# Sheet9.net
KiCad netlist of a schematic drawn in Altium Designer
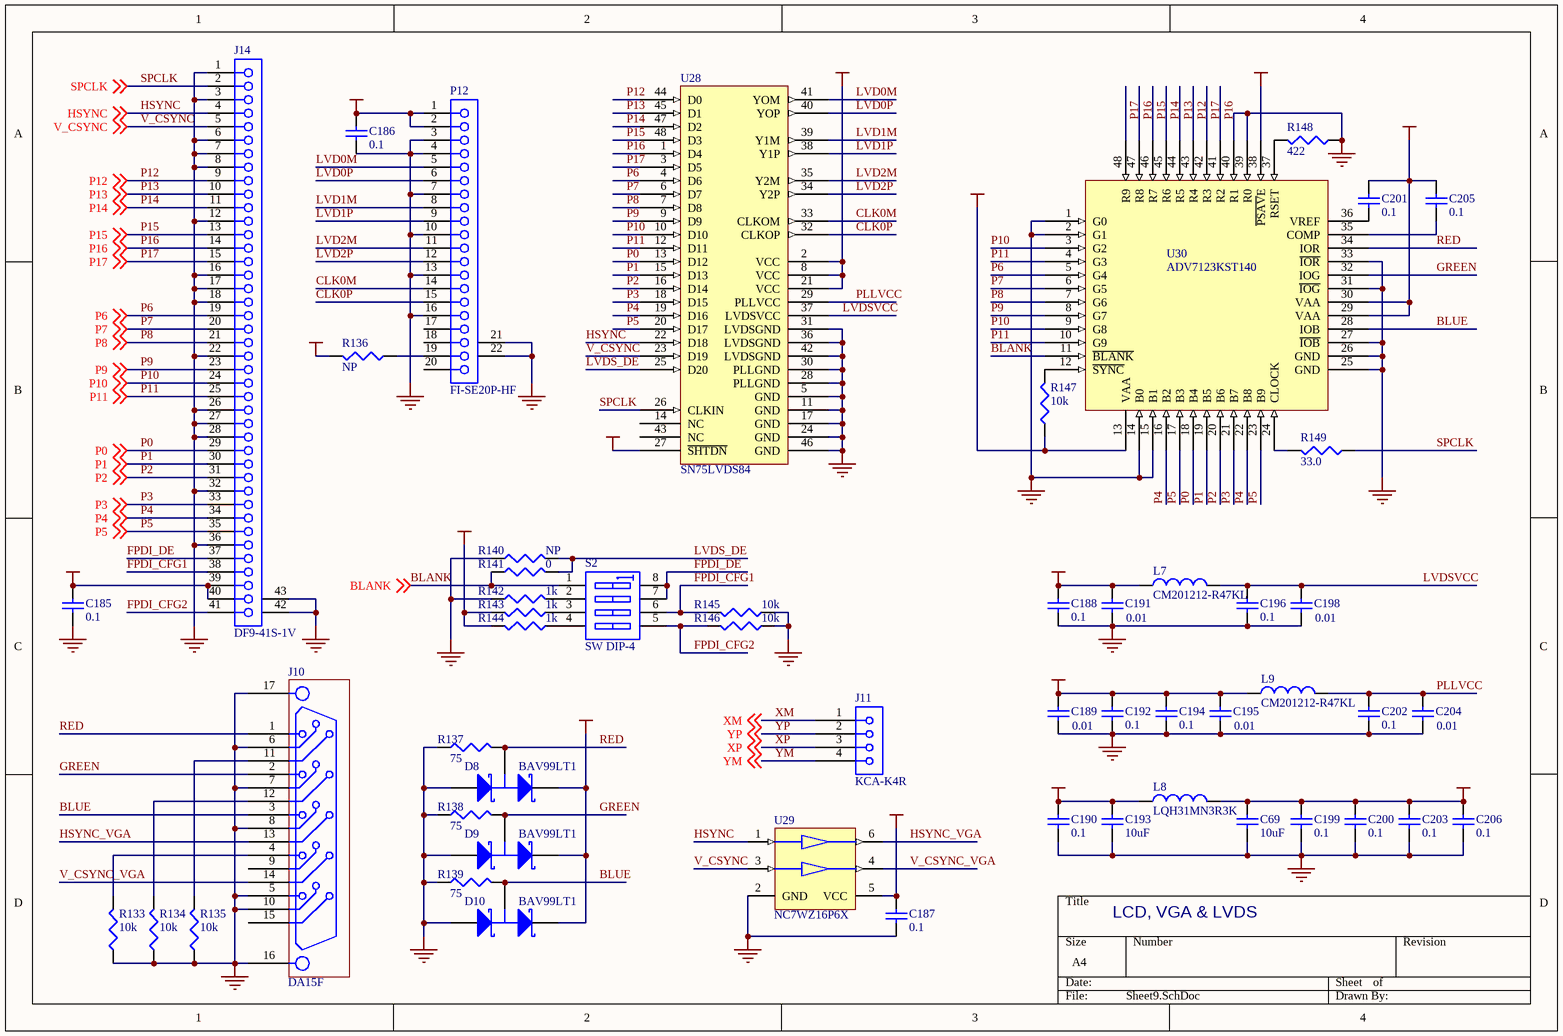
[diagram p0: Sheet9.SchDoc]

(export (version "E")
  (design (tool "Eeschema 10.0.6"))
  (components
    (comp (ref "C69")
      (value "10uF")
      (footprint "1206")
      (description "Ceramic Chip Capacitor - Standard")
      (fields (field (name "PUBLISHER") "Altium Limited"))
      (libsource (lib "KEMET Chip Capacitor") (part "C1206"))
    )
    (comp (ref "C185")
      (value "0.1")
      (footprint "0603")
      (description "Ceramic Chip Capacitor - Standard")
      (fields (field (name "PUBLISHER") "Altium Limited"))
      (libsource (lib "KEMET Chip Capacitor") (part "C0603"))
    )
    (comp (ref "C186")
      (value "0.1")
      (footprint "0603")
      (description "Ceramic Chip Capacitor - Standard")
      (fields (field (name "PUBLISHER") "Altium Limited"))
      (libsource (lib "KEMET Chip Capacitor") (part "C0603"))
    )
    (comp (ref "C187")
      (value "0.1")
      (footprint "0603")
      (description "Ceramic Chip Capacitor - Standard")
      (fields (field (name "PUBLISHER") "Altium Limited"))
      (libsource (lib "KEMET Chip Capacitor") (part "C0603"))
    )
    (comp (ref "C188")
      (value "0.1")
      (footprint "0603")
      (description "Ceramic Chip Capacitor - Standard")
      (fields (field (name "PUBLISHER") "Altium Limited"))
      (libsource (lib "KEMET Chip Capacitor") (part "C0603"))
    )
    (comp (ref "C189")
      (value "0.01")
      (footprint "0603")
      (description "Ceramic Chip Capacitor - Standard")
      (fields (field (name "PUBLISHER") "Altium Limited"))
      (libsource (lib "KEMET Chip Capacitor") (part "C0603"))
    )
    (comp (ref "C190")
      (value "0.1")
      (footprint "0603")
      (description "Ceramic Chip Capacitor - Standard")
      (fields (field (name "PUBLISHER") "Altium Limited"))
      (libsource (lib "KEMET Chip Capacitor") (part "C0603"))
    )
    (comp (ref "C191")
      (value "0.01")
      (footprint "0603")
      (description "Ceramic Chip Capacitor - Standard")
      (fields (field (name "PUBLISHER") "Altium Limited"))
      (libsource (lib "KEMET Chip Capacitor") (part "C0603"))
    )
    (comp (ref "C192")
      (value "0.1")
      (footprint "0603")
      (description "Ceramic Chip Capacitor - Standard")
      (fields (field (name "PUBLISHER") "Altium Limited"))
      (libsource (lib "KEMET Chip Capacitor") (part "C0603"))
    )
    (comp (ref "C193")
      (value "10uF")
      (footprint "1206")
      (description "Ceramic Chip Capacitor - Standard")
      (fields (field (name "PUBLISHER") "Altium Limited"))
      (libsource (lib "KEMET Chip Capacitor") (part "C1206"))
    )
    (comp (ref "C194")
      (value "0.1")
      (footprint "0603")
      (description "Ceramic Chip Capacitor - Standard")
      (fields (field (name "PUBLISHER") "Altium Limited"))
      (libsource (lib "KEMET Chip Capacitor") (part "C0603"))
    )
    (comp (ref "C195")
      (value "0.01")
      (footprint "0603")
      (description "Ceramic Chip Capacitor - Standard")
      (fields (field (name "PUBLISHER") "Altium Limited"))
      (libsource (lib "KEMET Chip Capacitor") (part "C0603"))
    )
    (comp (ref "C196")
      (value "0.1")
      (footprint "0603")
      (description "Ceramic Chip Capacitor - Standard")
      (fields (field (name "PUBLISHER") "Altium Limited"))
      (libsource (lib "KEMET Chip Capacitor") (part "C0603"))
    )
    (comp (ref "C198")
      (value "0.01")
      (footprint "0603")
      (description "Ceramic Chip Capacitor - Standard")
      (fields (field (name "PUBLISHER") "Altium Limited"))
      (libsource (lib "KEMET Chip Capacitor") (part "C0603"))
    )
    (comp (ref "C199")
      (value "0.1")
      (footprint "0603")
      (description "Ceramic Chip Capacitor - Standard")
      (fields (field (name "PUBLISHER") "Altium Limited"))
      (libsource (lib "KEMET Chip Capacitor") (part "C0603"))
    )
    (comp (ref "C200")
      (value "0.1")
      (footprint "0603")
      (description "Ceramic Chip Capacitor - Standard")
      (fields (field (name "PUBLISHER") "Altium Limited"))
      (libsource (lib "KEMET Chip Capacitor") (part "C0603"))
    )
    (comp (ref "C201")
      (value "0.1")
      (footprint "0603")
      (description "Ceramic Chip Capacitor - Standard")
      (fields (field (name "PUBLISHER") "Altium Limited"))
      (libsource (lib "KEMET Chip Capacitor") (part "C0603"))
    )
    (comp (ref "C202")
      (value "0.1")
      (footprint "0603")
      (description "Ceramic Chip Capacitor - Standard")
      (fields (field (name "PUBLISHER") "Altium Limited"))
      (libsource (lib "KEMET Chip Capacitor") (part "C0603"))
    )
    (comp (ref "C203")
      (value "0.1")
      (footprint "0603")
      (description "Ceramic Chip Capacitor - Standard")
      (fields (field (name "PUBLISHER") "Altium Limited"))
      (libsource (lib "KEMET Chip Capacitor") (part "C0603"))
    )
    (comp (ref "C204")
      (value "0.01")
      (footprint "0603")
      (description "Ceramic Chip Capacitor - Standard")
      (fields (field (name "PUBLISHER") "Altium Limited"))
      (libsource (lib "KEMET Chip Capacitor") (part "C0603"))
    )
    (comp (ref "C205")
      (value "0.1")
      (footprint "0603")
      (description "Ceramic Chip Capacitor - Standard")
      (fields (field (name "PUBLISHER") "Altium Limited"))
      (libsource (lib "KEMET Chip Capacitor") (part "C0603"))
    )
    (comp (ref "C206")
      (value "0.1")
      (footprint "0603")
      (description "Ceramic Chip Capacitor - Standard")
      (fields (field (name "PUBLISHER") "Altium Limited"))
      (libsource (lib "KEMET Chip Capacitor") (part "C0603"))
    )
    (comp (ref "D8")
      (value "BAV99LT1")
      (footprint "SOT23")
      (description "Schottky Barrier Double Diode")
      (fields (field (name "PUBLISHER") "Altium Limited"))
      (libsource (lib "Philips Discrete Diode - Schottky") (part "BAS40-04"))
    )
    (comp (ref "D9")
      (value "BAV99LT1")
      (footprint "SOT23")
      (description "Schottky Barrier Double Diode")
      (fields (field (name "PUBLISHER") "Altium Limited"))
      (libsource (lib "Philips Discrete Diode - Schottky") (part "BAS40-04"))
    )
    (comp (ref "D10")
      (value "BAV99LT1")
      (footprint "SOT23")
      (description "Schottky Barrier Double Diode")
      (fields (field (name "PUBLISHER") "Altium Limited"))
      (libsource (lib "Philips Discrete Diode - Schottky") (part "BAS40-04"))
    )
    (comp (ref "J10")
      (value "DA15F")
      (footprint "DA15F")
      (description "15pin DSUB High Density Female")
      (libsource (lib "MiscDev") (part "DA15F"))
    )
    (comp (ref "J11")
      (value "KCA-K4R")
      (footprint "KCAK4R")
      (description "Connector for ASTTouch Screen")
      (libsource (lib "MiscDev") (part "KCAK4R"))
    )
    (comp (ref "J14")
      (value "DF9-41S-1V")
      (footprint "DF9-41S-1V")
      (description "1mm Pitch SMT VESA FPDI-1")
      (libsource (lib "*") (part "DF9-41S-1V"))
    )
    (comp (ref "L7")
      (value "CM201212-R47KL")
      (footprint "INDC2012-0805")
      (description "Inductor")
      (fields (field (name "PUBLISHER") "Altium Limited"))
      (libsource (lib "Miscellaneous Devices") (part "Inductor"))
    )
    (comp (ref "L8")
      (value "LQH31MN3R3K")
      (footprint "INDC3216-1206")
      (description "Inductor")
      (fields (field (name "PUBLISHER") "Altium Limited"))
      (libsource (lib "Miscellaneous Devices") (part "Inductor"))
    )
    (comp (ref "L9")
      (value "CM201212-R47KL")
      (footprint "INDC2012-0805")
      (description "Inductor")
      (fields (field (name "PUBLISHER") "Altium Limited"))
      (libsource (lib "Miscellaneous Devices") (part "Inductor"))
    )
    (comp (ref "P12")
      (value "FI-SE20P-HF")
      (footprint "FI-SE20P-HF")
      (description "20PIN 1.25mm pitch")
      (libsource (lib "*") (part "FI-SE20P-HF"))
    )
    (comp (ref "R133")
      (value "10k")
      (footprint "CR1608-0603")
      (description "Resistor")
      (fields (field (name "PUBLISHER") "Altium Limited"))
      (libsource (lib "Miscellaneous Devices") (part "Res3"))
    )
    (comp (ref "R134")
      (value "10k")
      (footprint "CR1608-0603")
      (description "Resistor")
      (fields (field (name "PUBLISHER") "Altium Limited"))
      (libsource (lib "Miscellaneous Devices") (part "Res3"))
    )
    (comp (ref "R135")
      (value "10k")
      (footprint "CR1608-0603")
      (description "Resistor")
      (fields (field (name "PUBLISHER") "Altium Limited"))
      (libsource (lib "Miscellaneous Devices") (part "Res3"))
    )
    (comp (ref "R136")
      (value "NP")
      (footprint "CR1608-0603")
      (description "Resistor")
      (fields (field (name "PUBLISHER") "Altium Limited"))
      (libsource (lib "Miscellaneous Devices") (part "Res3"))
    )
    (comp (ref "R137")
      (value "75")
      (footprint "CR1608-0603")
      (description "Resistor")
      (fields (field (name "PUBLISHER") "Altium Limited"))
      (libsource (lib "Miscellaneous Devices") (part "Res3"))
    )
    (comp (ref "R138")
      (value "75")
      (footprint "CR1608-0603")
      (description "Resistor")
      (fields (field (name "PUBLISHER") "Altium Limited"))
      (libsource (lib "Miscellaneous Devices") (part "Res3"))
    )
    (comp (ref "R139")
      (value "75")
      (footprint "CR1608-0603")
      (description "Resistor")
      (fields (field (name "PUBLISHER") "Altium Limited"))
      (libsource (lib "Miscellaneous Devices") (part "Res3"))
    )
    (comp (ref "R140")
      (value "NP")
      (footprint "CR1608-0603")
      (description "Resistor")
      (fields (field (name "PUBLISHER") "Altium Limited"))
      (libsource (lib "Miscellaneous Devices") (part "Res3"))
    )
    (comp (ref "R141")
      (value "0")
      (footprint "CR1608-0603")
      (description "Resistor")
      (fields (field (name "PUBLISHER") "Altium Limited"))
      (libsource (lib "Miscellaneous Devices") (part "Res3"))
    )
    (comp (ref "R142")
      (value "1k")
      (footprint "CR1608-0603")
      (description "Resistor")
      (fields (field (name "PUBLISHER") "Altium Limited"))
      (libsource (lib "Miscellaneous Devices") (part "Res3"))
    )
    (comp (ref "R143")
      (value "1k")
      (footprint "CR1608-0603")
      (description "Resistor")
      (fields (field (name "PUBLISHER") "Altium Limited"))
      (libsource (lib "Miscellaneous Devices") (part "Res3"))
    )
    (comp (ref "R144")
      (value "1k")
      (footprint "CR1608-0603")
      (description "Resistor")
      (fields (field (name "PUBLISHER") "Altium Limited"))
      (libsource (lib "Miscellaneous Devices") (part "Res3"))
    )
    (comp (ref "R145")
      (value "10k")
      (footprint "CR1608-0603")
      (description "Resistor")
      (fields (field (name "PUBLISHER") "Altium Limited"))
      (libsource (lib "Miscellaneous Devices") (part "Res3"))
    )
    (comp (ref "R146")
      (value "10k")
      (footprint "CR1608-0603")
      (description "Resistor")
      (fields (field (name "PUBLISHER") "Altium Limited"))
      (libsource (lib "Miscellaneous Devices") (part "Res3"))
    )
    (comp (ref "R147")
      (value "10k")
      (footprint "CR1608-0603")
      (description "Resistor")
      (fields (field (name "PUBLISHER") "Altium Limited"))
      (libsource (lib "Miscellaneous Devices") (part "Res3"))
    )
    (comp (ref "R148")
      (value "422")
      (footprint "CR1608-0603")
      (description "Resistor")
      (fields (field (name "PUBLISHER") "Altium Limited"))
      (libsource (lib "Miscellaneous Devices") (part "Res3"))
    )
    (comp (ref "R149")
      (value "33.0")
      (footprint "CR1608-0603")
      (description "Resistor")
      (fields (field (name "Comment") "33") (field (name "PUBLISHER") "Altium Limited"))
      (libsource (lib "Miscellaneous Devices") (part "Res3"))
    )
    (comp (ref "S2")
      (value "SW DIP-4")
      (footprint "SO-G8/D6.6")
      (description "DIP Switch, 4 Position, SPST")
      (fields (field (name "PUBLISHER") "Altium Limited"))
      (libsource (lib "Miscellaneous Devices") (part "SW DIP-4"))
    )
    (comp (ref "U28")
      (value "SN75LVDS84")
      (footprint "TSSO12x8-48")
      (description "LVDS 18-Bit Color Flat Panel Display (FPD) Link")
      (libsource (lib "*") (part "SN75LVDS84"))
    )
    (comp (ref "U29")
      (value "NC7WZ16P6X")
      (footprint "SC88")
      (description "TinyLogic UHS Dual Buffer")
      (libsource (lib "*") (part "NC7WZ16P6X"))
    )
    (comp (ref "U30")
      (value "ADV7123KST140")
      (footprint "48A")
      (description "Triple 10-Bit High Speed Video DAC")
      (libsource (lib "ADV7123") (part "ADV7123"))
    )
  )
  (nets
    (net (code "1") (name "/BLUE") (class "Default")
      (node (ref "D10") (pin "3") (pinfunction "C_3") (pintype "passive"))
      (node (ref "J10") (pin "3") (pinfunction "3_3") (pintype "passive"))
      (node (ref "R139") (pin "2") (pinfunction "2_2") (pintype "passive"))
      (node (ref "U30") (pin "28") (pinfunction "IOB_28") (pintype "passive"))
    )
    (net (code "2") (name "/CLK0M") (class "Default")
      (node (ref "P12") (pin "14") (pinfunction "14_14") (pintype "passive"))
      (node (ref "U28") (pin "33") (pinfunction "CLKOM_33") (pintype "output"))
    )
    (net (code "3") (name "/CLK0P") (class "Default")
      (node (ref "P12") (pin "15") (pinfunction "15_15") (pintype "passive"))
      (node (ref "U28") (pin "32") (pinfunction "CLKOP_32") (pintype "output"))
    )
    (net (code "4") (name "/FPDI_CFG1") (class "Default")
      (node (ref "J14") (pin "38") (pinfunction "38_38") (pintype "passive"))
      (node (ref "R145") (pin "2") (pinfunction "2_2") (pintype "passive"))
      (node (ref "S2") (pin "6") (pinfunction "B3_6") (pintype "passive"))
    )
    (net (code "5") (name "/FPDI_CFG2") (class "Default")
      (node (ref "J14") (pin "41") (pinfunction "41_41") (pintype "passive"))
      (node (ref "R146") (pin "2") (pinfunction "2_2") (pintype "passive"))
      (node (ref "S2") (pin "5") (pinfunction "B4_5") (pintype "passive"))
    )
    (net (code "6") (name "/FPDI_DE") (class "Default")
      (node (ref "J14") (pin "37") (pinfunction "37_37") (pintype "passive"))
      (node (ref "S2") (pin "7") (pinfunction "B2_7") (pintype "passive"))
      (node (ref "S2") (pin "8") (pinfunction "B1_8") (pintype "passive"))
    )
    (net (code "7") (name "/GREEN") (class "Default")
      (node (ref "D9") (pin "3") (pinfunction "C_3") (pintype "passive"))
      (node (ref "J10") (pin "2") (pinfunction "2_2") (pintype "passive"))
      (node (ref "R138") (pin "2") (pinfunction "2_2") (pintype "passive"))
      (node (ref "U30") (pin "32") (pinfunction "IOG_32") (pintype "passive"))
    )
    (net (code "8") (name "/HSYNC_VGA") (class "Default")
      (node (ref "J10") (pin "13") (pinfunction "13_13") (pintype "passive"))
      (node (ref "U29") (pin "6") (pinfunction "Y_6") (pintype "output"))
    )
    (net (code "9") (name "/LVD0M") (class "Default")
      (node (ref "P12") (pin "5") (pinfunction "5_5") (pintype "passive"))
      (node (ref "U28") (pin "41") (pinfunction "YOM_41") (pintype "output"))
    )
    (net (code "10") (name "/LVD0P") (class "Default")
      (node (ref "P12") (pin "6") (pinfunction "6_6") (pintype "passive"))
      (node (ref "U28") (pin "40") (pinfunction "YOP_40") (pintype "output"))
    )
    (net (code "11") (name "/LVD1M") (class "Default")
      (node (ref "P12") (pin "8") (pinfunction "8_8") (pintype "passive"))
      (node (ref "U28") (pin "39") (pinfunction "Y1M_39") (pintype "output"))
    )
    (net (code "12") (name "/LVD1P") (class "Default")
      (node (ref "P12") (pin "9") (pinfunction "9_9") (pintype "passive"))
      (node (ref "U28") (pin "38") (pinfunction "Y1P_38") (pintype "output"))
    )
    (net (code "13") (name "/LVD2M") (class "Default")
      (node (ref "P12") (pin "11") (pinfunction "11_11") (pintype "passive"))
      (node (ref "U28") (pin "35") (pinfunction "Y2M_35") (pintype "output"))
    )
    (net (code "14") (name "/LVD2P") (class "Default")
      (node (ref "P12") (pin "12") (pinfunction "12_12") (pintype "passive"))
      (node (ref "U28") (pin "34") (pinfunction "Y2P_34") (pintype "output"))
    )
    (net (code "15") (name "/LVDSVCC") (class "Default")
      (node (ref "C196") (pin "1") (pinfunction "1_1") (pintype "passive"))
      (node (ref "C198") (pin "2") (pinfunction "2_2") (pintype "passive"))
      (node (ref "L7") (pin "2") (pinfunction "2_2") (pintype "passive"))
      (node (ref "U28") (pin "37") (pinfunction "LVDSVCC_37") (pintype "passive"))
    )
    (net (code "16") (name "/LVDS_DE") (class "Default")
      (node (ref "R140") (pin "2") (pinfunction "2_2") (pintype "passive"))
      (node (ref "R141") (pin "2") (pinfunction "2_2") (pintype "passive"))
      (node (ref "U28") (pin "25") (pinfunction "D20_25") (pintype "input"))
    )
    (net (code "17") (name "/PLLVCC") (class "Default")
      (node (ref "C202") (pin "1") (pinfunction "1_1") (pintype "passive"))
      (node (ref "C204") (pin "2") (pinfunction "2_2") (pintype "passive"))
      (node (ref "L9") (pin "2") (pinfunction "2_2") (pintype "passive"))
      (node (ref "U28") (pin "29") (pinfunction "PLLVCC_29") (pintype "passive"))
    )
    (net (code "18") (name "/RED") (class "Default")
      (node (ref "D8") (pin "3") (pinfunction "C_3") (pintype "passive"))
      (node (ref "J10") (pin "1") (pinfunction "1_1") (pintype "passive"))
      (node (ref "R137") (pin "2") (pinfunction "2_2") (pintype "passive"))
      (node (ref "U30") (pin "34") (pinfunction "IOR_34") (pintype "passive"))
    )
    (net (code "19") (name "/V_CSYNC_VGA") (class "Default")
      (node (ref "J10") (pin "14") (pinfunction "14_14") (pintype "passive"))
      (node (ref "U29") (pin "4") (pinfunction "Y_4") (pintype "output"))
    )
    (net (code "20") (name "BLANK") (class "Default")
      (node (ref "R141") (pin "1") (pinfunction "1_1") (pintype "passive"))
      (node (ref "S2") (pin "1") (pinfunction "A1_1") (pintype "passive"))
      (node (ref "U30") (pin "11") (pinfunction "~{BLANK}_11") (pintype "input"))
    )
    (net (code "21") (name "GND") (class "Default")
      (node (ref "C185") (pin "2") (pinfunction "2_2") (pintype "passive"))
      (node (ref "C186") (pin "2") (pinfunction "2_2") (pintype "passive"))
      (node (ref "C187") (pin "2") (pinfunction "2_2") (pintype "passive"))
      (node (ref "C188") (pin "2") (pinfunction "2_2") (pintype "passive"))
      (node (ref "C189") (pin "1") (pinfunction "1_1") (pintype "passive"))
      (node (ref "C190") (pin "2") (pinfunction "2_2") (pintype "passive"))
      (node (ref "C191") (pin "1") (pinfunction "1_1") (pintype "passive"))
      (node (ref "C192") (pin "2") (pinfunction "2_2") (pintype "passive"))
      (node (ref "C193") (pin "1") (pinfunction "1_1") (pintype "passive"))
      (node (ref "C194") (pin "2") (pinfunction "2_2") (pintype "passive"))
      (node (ref "C195") (pin "1") (pinfunction "1_1") (pintype "passive"))
      (node (ref "C196") (pin "2") (pinfunction "2_2") (pintype "passive"))
      (node (ref "C198") (pin "1") (pinfunction "1_1") (pintype "passive"))
      (node (ref "C199") (pin "2") (pinfunction "2_2") (pintype "passive"))
      (node (ref "C200") (pin "2") (pinfunction "2_2") (pintype "passive"))
      (node (ref "C202") (pin "2") (pinfunction "2_2") (pintype "passive"))
      (node (ref "C203") (pin "2") (pinfunction "2_2") (pintype "passive"))
      (node (ref "C204") (pin "1") (pinfunction "1_1") (pintype "passive"))
      (node (ref "C206") (pin "2") (pinfunction "2_2") (pintype "passive"))
      (node (ref "C69") (pin "1") (pinfunction "1_1") (pintype "passive"))
      (node (ref "D10") (pin "1") (pinfunction "A_1") (pintype "passive"))
      (node (ref "D8") (pin "1") (pinfunction "A_1") (pintype "passive"))
      (node (ref "D9") (pin "1") (pinfunction "A_1") (pintype "passive"))
      (node (ref "J10") (pin "10") (pinfunction "10_10") (pintype "passive"))
      (node (ref "J10") (pin "16") (pinfunction "16_16") (pintype "passive"))
      (node (ref "J10") (pin "17") (pinfunction "17_17") (pintype "passive"))
      (node (ref "J10") (pin "5") (pinfunction "5_5") (pintype "passive"))
      (node (ref "J10") (pin "6") (pinfunction "6_6") (pintype "passive"))
      (node (ref "J10") (pin "7") (pinfunction "7_7") (pintype "passive"))
      (node (ref "J10") (pin "8") (pinfunction "8_8") (pintype "passive"))
      (node (ref "J14") (pin "1") (pinfunction "1_1") (pintype "passive"))
      (node (ref "J14") (pin "12") (pinfunction "12_12") (pintype "passive"))
      (node (ref "J14") (pin "16") (pinfunction "16_16") (pintype "passive"))
      (node (ref "J14") (pin "17") (pinfunction "17_17") (pintype "passive"))
      (node (ref "J14") (pin "18") (pinfunction "18_18") (pintype "passive"))
      (node (ref "J14") (pin "22") (pinfunction "22_22") (pintype "passive"))
      (node (ref "J14") (pin "26") (pinfunction "26_26") (pintype "passive"))
      (node (ref "J14") (pin "27") (pinfunction "27_27") (pintype "passive"))
      (node (ref "J14") (pin "28") (pinfunction "28_28") (pintype "passive"))
      (node (ref "J14") (pin "3") (pinfunction "3_3") (pintype "passive"))
      (node (ref "J14") (pin "32") (pinfunction "32_32") (pintype "passive"))
      (node (ref "J14") (pin "36") (pinfunction "36_36") (pintype "passive"))
      (node (ref "J14") (pin "42") (pinfunction "MH2_42") (pintype "passive"))
      (node (ref "J14") (pin "43") (pinfunction "MH1_43") (pintype "passive"))
      (node (ref "J14") (pin "6") (pinfunction "6_6") (pintype "passive"))
      (node (ref "J14") (pin "7") (pinfunction "7_7") (pintype "passive"))
      (node (ref "J14") (pin "8") (pinfunction "8_8") (pintype "passive"))
      (node (ref "P12") (pin "10") (pinfunction "10_10") (pintype "passive"))
      (node (ref "P12") (pin "13") (pinfunction "13_13") (pintype "passive"))
      (node (ref "P12") (pin "16") (pinfunction "16_16") (pintype "passive"))
      (node (ref "P12") (pin "21") (pinfunction "21_21") (pintype "passive"))
      (node (ref "P12") (pin "22") (pinfunction "22_22") (pintype "passive"))
      (node (ref "P12") (pin "3") (pinfunction "3_3") (pintype "passive"))
      (node (ref "P12") (pin "4") (pinfunction "4_4") (pintype "passive"))
      (node (ref "P12") (pin "7") (pinfunction "7_7") (pintype "passive"))
      (node (ref "R133") (pin "1") (pinfunction "1_1") (pintype "passive"))
      (node (ref "R134") (pin "1") (pinfunction "1_1") (pintype "passive"))
      (node (ref "R135") (pin "1") (pinfunction "1_1") (pintype "passive"))
      (node (ref "R137") (pin "1") (pinfunction "1_1") (pintype "passive"))
      (node (ref "R138") (pin "1") (pinfunction "1_1") (pintype "passive"))
      (node (ref "R139") (pin "1") (pinfunction "1_1") (pintype "passive"))
      (node (ref "R140") (pin "1") (pinfunction "1_1") (pintype "passive"))
      (node (ref "R142") (pin "1") (pinfunction "1_1") (pintype "passive"))
      (node (ref "R145") (pin "1") (pinfunction "1_1") (pintype "passive"))
      (node (ref "R146") (pin "1") (pinfunction "1_1") (pintype "passive"))
      (node (ref "R148") (pin "1") (pinfunction "1_1") (pintype "passive"))
      (node (ref "U28") (pin "11") (pinfunction "GND_11") (pintype "passive"))
      (node (ref "U28") (pin "17") (pinfunction "GND_17") (pintype "passive"))
      (node (ref "U28") (pin "24") (pinfunction "GND_24") (pintype "passive"))
      (node (ref "U28") (pin "28") (pinfunction "PLLGND_28") (pintype "passive"))
      (node (ref "U28") (pin "30") (pinfunction "PLLGND_30") (pintype "passive"))
      (node (ref "U28") (pin "31") (pinfunction "LVDSGND_31") (pintype "passive"))
      (node (ref "U28") (pin "36") (pinfunction "LVDSGND_36") (pintype "passive"))
      (node (ref "U28") (pin "42") (pinfunction "LVDSGND_42") (pintype "passive"))
      (node (ref "U28") (pin "46") (pinfunction "GND_46") (pintype "passive"))
      (node (ref "U28") (pin "5") (pinfunction "GND_5") (pintype "passive"))
      (node (ref "U29") (pin "2") (pinfunction "GND_2") (pintype "passive"))
      (node (ref "U30") (pin "1") (pinfunction "G0_1") (pintype "input"))
      (node (ref "U30") (pin "14") (pinfunction "B0_14") (pintype "input"))
      (node (ref "U30") (pin "15") (pinfunction "B1_15") (pintype "input"))
      (node (ref "U30") (pin "2") (pinfunction "G1_2") (pintype "input"))
      (node (ref "U30") (pin "25") (pinfunction "GND_25") (pintype "passive"))
      (node (ref "U30") (pin "26") (pinfunction "GND_26") (pintype "passive"))
      (node (ref "U30") (pin "27") (pinfunction "~{IOB}_27") (pintype "passive"))
      (node (ref "U30") (pin "31") (pinfunction "~{IOG}_31") (pintype "passive"))
      (node (ref "U30") (pin "33") (pinfunction "~{IOR}_33") (pintype "passive"))
      (node (ref "U30") (pin "39") (pinfunction "R0_39") (pintype "input"))
      (node (ref "U30") (pin "40") (pinfunction "R1_40") (pintype "input"))
    )
    (net (code "22") (name "HSYNC") (class "Default")
      (node (ref "J14") (pin "4") (pinfunction "4_4") (pintype "passive"))
      (node (ref "U28") (pin "22") (pinfunction "D18_22") (pintype "input"))
      (node (ref "U29") (pin "1") (pinfunction "A_1") (pintype "input"))
    )
    (net (code "23") (name "Net-(J10-Pad4)") (class "Default")
      (node (ref "J10") (pin "4") (pinfunction "4_4") (pintype "passive"))
      (node (ref "R133") (pin "2") (pinfunction "2_2") (pintype "passive"))
    )
    (net (code "24") (name "Net-(J10-Pad11)") (class "Default")
      (node (ref "J10") (pin "11") (pinfunction "11_11") (pintype "passive"))
      (node (ref "R135") (pin "2") (pinfunction "2_2") (pintype "passive"))
    )
    (net (code "25") (name "Net-(J10-Pad12)") (class "Default")
      (node (ref "J10") (pin "12") (pinfunction "12_12") (pintype "passive"))
      (node (ref "R134") (pin "2") (pinfunction "2_2") (pintype "passive"))
    )
    (net (code "26") (name "Net-(P12-Pad19)") (class "Default")
      (node (ref "P12") (pin "19") (pinfunction "19_19") (pintype "passive"))
      (node (ref "R136") (pin "1") (pinfunction "1_1") (pintype "passive"))
    )
    (net (code "27") (name "Net-(S2-A2)") (class "Default")
      (node (ref "R142") (pin "2") (pinfunction "2_2") (pintype "passive"))
      (node (ref "S2") (pin "2") (pinfunction "A2_2") (pintype "passive"))
    )
    (net (code "28") (name "Net-(S2-A3)") (class "Default")
      (node (ref "R143") (pin "1") (pinfunction "1_1") (pintype "passive"))
      (node (ref "S2") (pin "3") (pinfunction "A3_3") (pintype "passive"))
    )
    (net (code "29") (name "Net-(S2-A4)") (class "Default")
      (node (ref "R144") (pin "1") (pinfunction "1_1") (pintype "passive"))
      (node (ref "S2") (pin "4") (pinfunction "A4_4") (pintype "passive"))
    )
    (net (code "30") (name "Net-(U30-CLOCK)") (class "Default")
      (node (ref "R149") (pin "2") (pinfunction "2_2") (pintype "passive"))
      (node (ref "U30") (pin "24") (pinfunction "CLOCK_24") (pintype "input"))
    )
    (net (code "31") (name "Net-(U30-COMP)") (class "Default")
      (node (ref "C205") (pin "2") (pinfunction "2_2") (pintype "passive"))
      (node (ref "U30") (pin "35") (pinfunction "COMP_35") (pintype "passive"))
    )
    (net (code "32") (name "Net-(U30-RSET)") (class "Default")
      (node (ref "R148") (pin "2") (pinfunction "2_2") (pintype "passive"))
      (node (ref "U30") (pin "37") (pinfunction "RSET_37") (pintype "input"))
    )
    (net (code "33") (name "Net-(U30-VREF)") (class "Default")
      (node (ref "C201") (pin "2") (pinfunction "2_2") (pintype "passive"))
      (node (ref "U30") (pin "36") (pinfunction "VREF_36") (pintype "passive"))
    )
    (net (code "34") (name "Net-(U30-~{SYNC})") (class "Default")
      (node (ref "R147") (pin "2") (pinfunction "2_2") (pintype "passive"))
      (node (ref "U30") (pin "12") (pinfunction "~{SYNC}_12") (pintype "input"))
    )
    (net (code "35") (name "P0") (class "Default")
      (node (ref "J14") (pin "29") (pinfunction "29_29") (pintype "passive"))
      (node (ref "U28") (pin "13") (pinfunction "D12_13") (pintype "input"))
      (node (ref "U30") (pin "18") (pinfunction "B4_18") (pintype "input"))
    )
    (net (code "36") (name "P1") (class "Default")
      (node (ref "J14") (pin "30") (pinfunction "30_30") (pintype "passive"))
      (node (ref "U28") (pin "15") (pinfunction "D13_15") (pintype "input"))
      (node (ref "U30") (pin "19") (pinfunction "B5_19") (pintype "input"))
    )
    (net (code "37") (name "P2") (class "Default")
      (node (ref "J14") (pin "31") (pinfunction "31_31") (pintype "passive"))
      (node (ref "U28") (pin "16") (pinfunction "D14_16") (pintype "input"))
      (node (ref "U30") (pin "20") (pinfunction "B6_20") (pintype "input"))
    )
    (net (code "38") (name "P3") (class "Default")
      (node (ref "J14") (pin "33") (pinfunction "33_33") (pintype "passive"))
      (node (ref "U28") (pin "18") (pinfunction "D15_18") (pintype "input"))
      (node (ref "U30") (pin "21") (pinfunction "B7_21") (pintype "input"))
    )
    (net (code "39") (name "P4") (class "Default")
      (node (ref "J14") (pin "34") (pinfunction "34_34") (pintype "passive"))
      (node (ref "U28") (pin "19") (pinfunction "D16_19") (pintype "input"))
      (node (ref "U30") (pin "16") (pinfunction "B2_16") (pintype "input"))
      (node (ref "U30") (pin "22") (pinfunction "B8_22") (pintype "input"))
    )
    (net (code "40") (name "P5") (class "Default")
      (node (ref "J14") (pin "35") (pinfunction "35_35") (pintype "passive"))
      (node (ref "U28") (pin "20") (pinfunction "D17_20") (pintype "input"))
      (node (ref "U30") (pin "17") (pinfunction "B3_17") (pintype "input"))
      (node (ref "U30") (pin "23") (pinfunction "B9_23") (pintype "input"))
    )
    (net (code "41") (name "P6") (class "Default")
      (node (ref "J14") (pin "19") (pinfunction "19_19") (pintype "passive"))
      (node (ref "U28") (pin "4") (pinfunction "D6_4") (pintype "input"))
      (node (ref "U30") (pin "5") (pinfunction "G4_5") (pintype "input"))
    )
    (net (code "42") (name "P7") (class "Default")
      (node (ref "J14") (pin "20") (pinfunction "20_20") (pintype "passive"))
      (node (ref "U28") (pin "6") (pinfunction "D7_6") (pintype "input"))
      (node (ref "U30") (pin "6") (pinfunction "G5_6") (pintype "input"))
    )
    (net (code "43") (name "P8") (class "Default")
      (node (ref "J14") (pin "21") (pinfunction "21_21") (pintype "passive"))
      (node (ref "U28") (pin "7") (pinfunction "D8_7") (pintype "input"))
      (node (ref "U30") (pin "7") (pinfunction "G6_7") (pintype "input"))
    )
    (net (code "44") (name "P9") (class "Default")
      (node (ref "J14") (pin "23") (pinfunction "23_23") (pintype "passive"))
      (node (ref "U28") (pin "9") (pinfunction "D9_9") (pintype "input"))
      (node (ref "U30") (pin "8") (pinfunction "G7_8") (pintype "input"))
    )
    (net (code "45") (name "P10") (class "Default")
      (node (ref "J14") (pin "24") (pinfunction "24_24") (pintype "passive"))
      (node (ref "U28") (pin "10") (pinfunction "D10_10") (pintype "input"))
      (node (ref "U30") (pin "3") (pinfunction "G2_3") (pintype "input"))
      (node (ref "U30") (pin "9") (pinfunction "G8_9") (pintype "input"))
    )
    (net (code "46") (name "P11") (class "Default")
      (node (ref "J14") (pin "25") (pinfunction "25_25") (pintype "passive"))
      (node (ref "U28") (pin "12") (pinfunction "D11_12") (pintype "input"))
      (node (ref "U30") (pin "10") (pinfunction "G9_10") (pintype "input"))
      (node (ref "U30") (pin "4") (pinfunction "G3_4") (pintype "input"))
    )
    (net (code "47") (name "P12") (class "Default")
      (node (ref "J14") (pin "9") (pinfunction "9_9") (pintype "passive"))
      (node (ref "U28") (pin "44") (pinfunction "D0_44") (pintype "input"))
      (node (ref "U30") (pin "43") (pinfunction "R4_43") (pintype "input"))
    )
    (net (code "48") (name "P13") (class "Default")
      (node (ref "J14") (pin "10") (pinfunction "10_10") (pintype "passive"))
      (node (ref "U28") (pin "45") (pinfunction "D1_45") (pintype "input"))
      (node (ref "U30") (pin "44") (pinfunction "R5_44") (pintype "input"))
    )
    (net (code "49") (name "P14") (class "Default")
      (node (ref "J14") (pin "11") (pinfunction "11_11") (pintype "passive"))
      (node (ref "U28") (pin "47") (pinfunction "D2_47") (pintype "input"))
      (node (ref "U30") (pin "45") (pinfunction "R6_45") (pintype "input"))
    )
    (net (code "50") (name "P15") (class "Default")
      (node (ref "J14") (pin "13") (pinfunction "13_13") (pintype "passive"))
      (node (ref "U28") (pin "48") (pinfunction "D3_48") (pintype "input"))
      (node (ref "U30") (pin "46") (pinfunction "R7_46") (pintype "input"))
    )
    (net (code "51") (name "P16") (class "Default")
      (node (ref "J14") (pin "14") (pinfunction "14_14") (pintype "passive"))
      (node (ref "U28") (pin "1") (pinfunction "D4_1") (pintype "input"))
      (node (ref "U30") (pin "41") (pinfunction "R2_41") (pintype "input"))
      (node (ref "U30") (pin "47") (pinfunction "R8_47") (pintype "input"))
    )
    (net (code "52") (name "P17") (class "Default")
      (node (ref "J14") (pin "15") (pinfunction "15_15") (pintype "passive"))
      (node (ref "U28") (pin "3") (pinfunction "D5_3") (pintype "input"))
      (node (ref "U30") (pin "42") (pinfunction "R3_42") (pintype "input"))
      (node (ref "U30") (pin "48") (pinfunction "R9_48") (pintype "input"))
    )
    (net (code "53") (name "SPCLK") (class "Default")
      (node (ref "J14") (pin "2") (pinfunction "2_2") (pintype "passive"))
      (node (ref "R149") (pin "1") (pinfunction "1_1") (pintype "passive"))
      (node (ref "U28") (pin "26") (pinfunction "CLKIN_26") (pintype "input"))
    )
    (net (code "54") (name "VCC5V0") (class "Default")
      (node (ref "C190") (pin "1") (pinfunction "1_1") (pintype "passive"))
      (node (ref "C193") (pin "2") (pinfunction "2_2") (pintype "passive"))
      (node (ref "L8") (pin "1") (pinfunction "1_1") (pintype "passive"))
    )
    (net (code "55") (name "VCC5V0_VGA") (class "Default")
      (node (ref "C187") (pin "1") (pinfunction "1_1") (pintype "passive"))
      (node (ref "C199") (pin "1") (pinfunction "1_1") (pintype "passive"))
      (node (ref "C200") (pin "1") (pinfunction "1_1") (pintype "passive"))
      (node (ref "C201") (pin "1") (pinfunction "1_1") (pintype "passive"))
      (node (ref "C203") (pin "1") (pinfunction "1_1") (pintype "passive"))
      (node (ref "C205") (pin "1") (pinfunction "1_1") (pintype "passive"))
      (node (ref "C206") (pin "1") (pinfunction "1_1") (pintype "passive"))
      (node (ref "C69") (pin "2") (pinfunction "2_2") (pintype "passive"))
      (node (ref "D10") (pin "2") (pinfunction "K_2") (pintype "passive"))
      (node (ref "D8") (pin "2") (pinfunction "K_2") (pintype "passive"))
      (node (ref "D9") (pin "2") (pinfunction "K_2") (pintype "passive"))
      (node (ref "L8") (pin "2") (pinfunction "2_2") (pintype "passive"))
      (node (ref "R147") (pin "1") (pinfunction "1_1") (pintype "passive"))
      (node (ref "U29") (pin "5") (pinfunction "VCC_5") (pintype "passive"))
      (node (ref "U30") (pin "13") (pinfunction "VAA_13") (pintype "passive"))
      (node (ref "U30") (pin "29") (pinfunction "VAA_29") (pintype "passive"))
      (node (ref "U30") (pin "30") (pinfunction "VAA_30") (pintype "passive"))
      (node (ref "U30") (pin "38") (pinfunction "~{PSAV}E_38") (pintype "input"))
    )
    (net (code "56") (name "VCCIO") (class "Default")
      (node (ref "C185") (pin "1") (pinfunction "1_1") (pintype "passive"))
      (node (ref "C186") (pin "1") (pinfunction "1_1") (pintype "passive"))
      (node (ref "C188") (pin "1") (pinfunction "1_1") (pintype "passive"))
      (node (ref "C189") (pin "2") (pinfunction "2_2") (pintype "passive"))
      (node (ref "C191") (pin "2") (pinfunction "2_2") (pintype "passive"))
      (node (ref "C192") (pin "1") (pinfunction "1_1") (pintype "passive"))
      (node (ref "C194") (pin "1") (pinfunction "1_1") (pintype "passive"))
      (node (ref "C195") (pin "2") (pinfunction "2_2") (pintype "passive"))
      (node (ref "J14") (pin "39") (pinfunction "39_39") (pintype "passive"))
      (node (ref "J14") (pin "40") (pinfunction "40_40") (pintype "passive"))
      (node (ref "L7") (pin "1") (pinfunction "1_1") (pintype "passive"))
      (node (ref "L9") (pin "1") (pinfunction "1_1") (pintype "passive"))
      (node (ref "P12") (pin "1") (pinfunction "1_1") (pintype "passive"))
      (node (ref "P12") (pin "2") (pinfunction "2_2") (pintype "passive"))
      (node (ref "R136") (pin "2") (pinfunction "2_2") (pintype "passive"))
      (node (ref "R143") (pin "2") (pinfunction "2_2") (pintype "passive"))
      (node (ref "R144") (pin "2") (pinfunction "2_2") (pintype "passive"))
      (node (ref "U28") (pin "2") (pinfunction "VCC_2") (pintype "passive"))
      (node (ref "U28") (pin "21") (pinfunction "VCC_21") (pintype "passive"))
      (node (ref "U28") (pin "27") (pinfunction "~{SHTDN}_27") (pintype "passive"))
      (node (ref "U28") (pin "8") (pinfunction "VCC_8") (pintype "passive"))
    )
    (net (code "57") (name "V_CSYNC") (class "Default")
      (node (ref "J14") (pin "5") (pinfunction "5_5") (pintype "passive"))
      (node (ref "U28") (pin "23") (pinfunction "D19_23") (pintype "input"))
      (node (ref "U29") (pin "3") (pinfunction "B_3") (pintype "input"))
    )
    (net (code "58") (name "XM") (class "Default")
      (node (ref "J11") (pin "1") (pinfunction "1_1") (pintype "passive"))
    )
    (net (code "59") (name "XP") (class "Default")
      (node (ref "J11") (pin "3") (pinfunction "3_3") (pintype "passive"))
    )
    (net (code "60") (name "YM") (class "Default")
      (node (ref "J11") (pin "4") (pinfunction "4_4") (pintype "passive"))
    )
    (net (code "61") (name "YP") (class "Default")
      (node (ref "J11") (pin "2") (pinfunction "2_2") (pintype "passive"))
    )
    (net (code "62") (name "unconnected-(J10-Pad9)") (class "Default")
      (node (ref "J10") (pin "9") (pinfunction "9_9") (pintype "passive"))
    )
    (net (code "63") (name "unconnected-(J10-Pad15)") (class "Default")
      (node (ref "J10") (pin "15") (pinfunction "15_15") (pintype "passive"))
    )
    (net (code "64") (name "unconnected-(P12-Pad17)") (class "Default")
      (node (ref "P12") (pin "17") (pinfunction "17_17") (pintype "passive"))
    )
    (net (code "65") (name "unconnected-(P12-Pad18)") (class "Default")
      (node (ref "P12") (pin "18") (pinfunction "18_18") (pintype "passive"))
    )
    (net (code "66") (name "unconnected-(P12-Pad20)") (class "Default")
      (node (ref "P12") (pin "20") (pinfunction "20_20") (pintype "passive"))
    )
    (net (code "67") (name "unconnected-(U28-NC-Pad14)") (class "Default")
      (node (ref "U28") (pin "14") (pinfunction "NC_14") (pintype "passive"))
    )
    (net (code "68") (name "unconnected-(U28-NC-Pad43)") (class "Default")
      (node (ref "U28") (pin "43") (pinfunction "NC_43") (pintype "passive"))
    )
  )
)
